# power.net
KiCad netlist of a schematic drawn in EAGLE
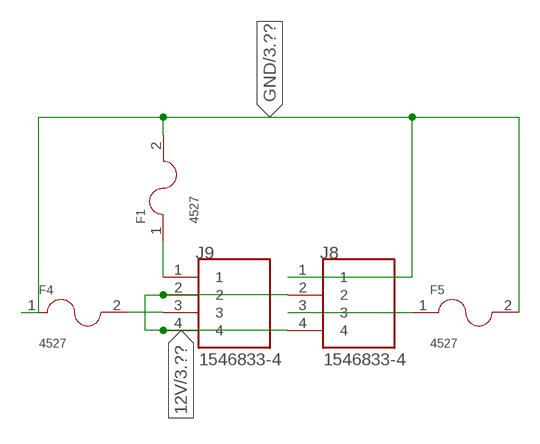
[diagram p0: schematic, sheet 2]
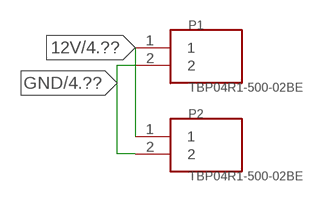
[diagram p1: schematic, sheet 3]
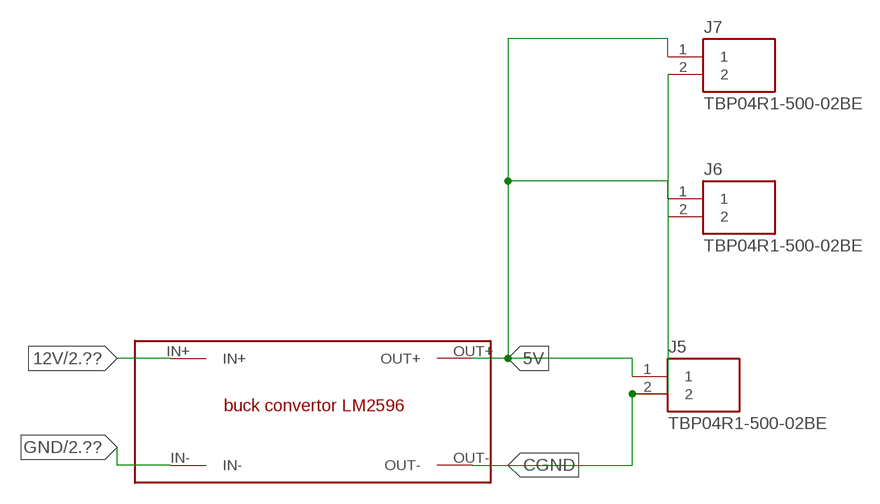
[diagram p2: schematic, sheet 4]

(export (version "E")
  (design (tool "Eeschema 10.0.6"))
  (components
    (comp (ref "F1")
      (value "4527")
      (footprint "eagle-import:FUSE_4527")
      (fields (field (name "MF") "Keystone"))
      (libsource (lib "eagle-import") (part "4527"))
    )
    (comp (ref "F4")
      (value "4527")
      (footprint "eagle-import:FUSE_4527")
      (fields (field (name "MF") "Keystone"))
      (libsource (lib "eagle-import") (part "4527"))
    )
    (comp (ref "F5")
      (value "4527")
      (footprint "eagle-import:FUSE_4527")
      (fields (field (name "MF") "Keystone"))
      (libsource (lib "eagle-import") (part "4527"))
    )
    (comp (ref "J8")
      (value "1546833-4")
      (footprint "eagle-import:TE_1546833-4")
      (fields (field (name "MF") "TE Connectivity"))
      (libsource (lib "eagle-import") (part "1546833-4"))
    )
    (comp (ref "J9")
      (value "1546833-4")
      (footprint "eagle-import:TE_1546833-4")
      (fields (field (name "MF") "TE Connectivity"))
      (libsource (lib "eagle-import") (part "1546833-4"))
    )
    (comp (ref "J5")
      (value "TBP04R1-500-02BE")
      (footprint "eagle-import:CUI_TBP04R1-500-02BE")
      (fields (field (name "MF") "Same Sky"))
      (libsource (lib "eagle-import") (part "TBP04R1-500-02BE"))
    )
    (comp (ref "J6")
      (value "TBP04R1-500-02BE")
      (footprint "eagle-import:CUI_TBP04R1-500-02BE")
      (fields (field (name "MF") "Same Sky"))
      (libsource (lib "eagle-import") (part "TBP04R1-500-02BE"))
    )
    (comp (ref "J7")
      (value "TBP04R1-500-02BE")
      (footprint "eagle-import:CUI_TBP04R1-500-02BE")
      (fields (field (name "MF") "Same Sky"))
      (libsource (lib "eagle-import") (part "TBP04R1-500-02BE"))
    )
    (comp (ref "U$1")
      (value "LM2596")
      (footprint "eagle-import:LM2596")
      (libsource (lib "eagle-import") (part "LM2596"))
    )
    (comp (ref "P1")
      (value "TBP04R1-500-02BE")
      (footprint "eagle-import:CUI_TBP04R1-500-02BE")
      (fields (field (name "MF") "Same Sky"))
      (libsource (lib "eagle-import") (part "TBP04R1-500-02BE"))
    )
    (comp (ref "P2")
      (value "TBP04R1-500-02BE")
      (footprint "eagle-import:CUI_TBP04R1-500-02BE")
      (fields (field (name "MF") "Same Sky"))
      (libsource (lib "eagle-import") (part "TBP04R1-500-02BE"))
    )
  )
  (nets
    (net (code "1") (name "5V") (class "Default")
      (node (ref "J5") (pin "1") (pinfunction "1_1") (pintype "passive"))
      (node (ref "J6") (pin "1") (pinfunction "1_1") (pintype "passive"))
      (node (ref "J7") (pin "1") (pinfunction "1_1") (pintype "passive"))
      (node (ref "U$1") (pin "OUT+") (pinfunction "OUT+_OUT+") (pintype "bidirectional"))
    )
    (net (code "2") (name "12V") (class "Default")
      (node (ref "J8") (pin "2") (pinfunction "2_2") (pintype "passive"))
      (node (ref "J8") (pin "4") (pinfunction "4_4") (pintype "passive"))
      (node (ref "J9") (pin "2") (pinfunction "2_2") (pintype "passive"))
      (node (ref "J9") (pin "4") (pinfunction "4_4") (pintype "passive"))
      (node (ref "P1") (pin "1") (pinfunction "1_1") (pintype "passive"))
      (node (ref "P2") (pin "1") (pinfunction "1_1") (pintype "passive"))
      (node (ref "U$1") (pin "IN+") (pinfunction "IN+_IN+") (pintype "bidirectional"))
    )
    (net (code "3") (name "CGND") (class "Default")
      (node (ref "J5") (pin "2") (pinfunction "2_2") (pintype "passive"))
      (node (ref "J6") (pin "2") (pinfunction "2_2") (pintype "passive"))
      (node (ref "J7") (pin "2") (pinfunction "2_2") (pintype "passive"))
      (node (ref "U$1") (pin "OUT-") (pinfunction "OUT-_OUT-") (pintype "bidirectional"))
    )
    (net (code "4") (name "GND") (class "Default")
      (node (ref "F1") (pin "2") (pinfunction "2_2") (pintype "passive"))
      (node (ref "F4") (pin "1") (pinfunction "1_1") (pintype "passive"))
      (node (ref "F5") (pin "2") (pinfunction "2_2") (pintype "passive"))
      (node (ref "J8") (pin "1") (pinfunction "1_1") (pintype "passive"))
      (node (ref "P1") (pin "2") (pinfunction "2_2") (pintype "passive"))
      (node (ref "P2") (pin "2") (pinfunction "2_2") (pintype "passive"))
      (node (ref "U$1") (pin "IN-") (pinfunction "IN-_IN-") (pintype "bidirectional"))
    )
    (net (code "5") (name "Net-(F1-Pad1)") (class "Default")
      (node (ref "F1") (pin "1") (pinfunction "1_1") (pintype "passive"))
      (node (ref "J9") (pin "1") (pinfunction "1_1") (pintype "passive"))
    )
    (net (code "6") (name "Net-(F4-Pad2)") (class "Default")
      (node (ref "F4") (pin "2") (pinfunction "2_2") (pintype "passive"))
      (node (ref "J9") (pin "3") (pinfunction "3_3") (pintype "passive"))
    )
    (net (code "7") (name "Net-(F5-Pad1)") (class "Default")
      (node (ref "F5") (pin "1") (pinfunction "1_1") (pintype "passive"))
      (node (ref "J8") (pin "3") (pinfunction "3_3") (pintype "passive"))
    )
  )
)
